# mian.net
KiCad netlist of a schematic drawn in Altium Designer
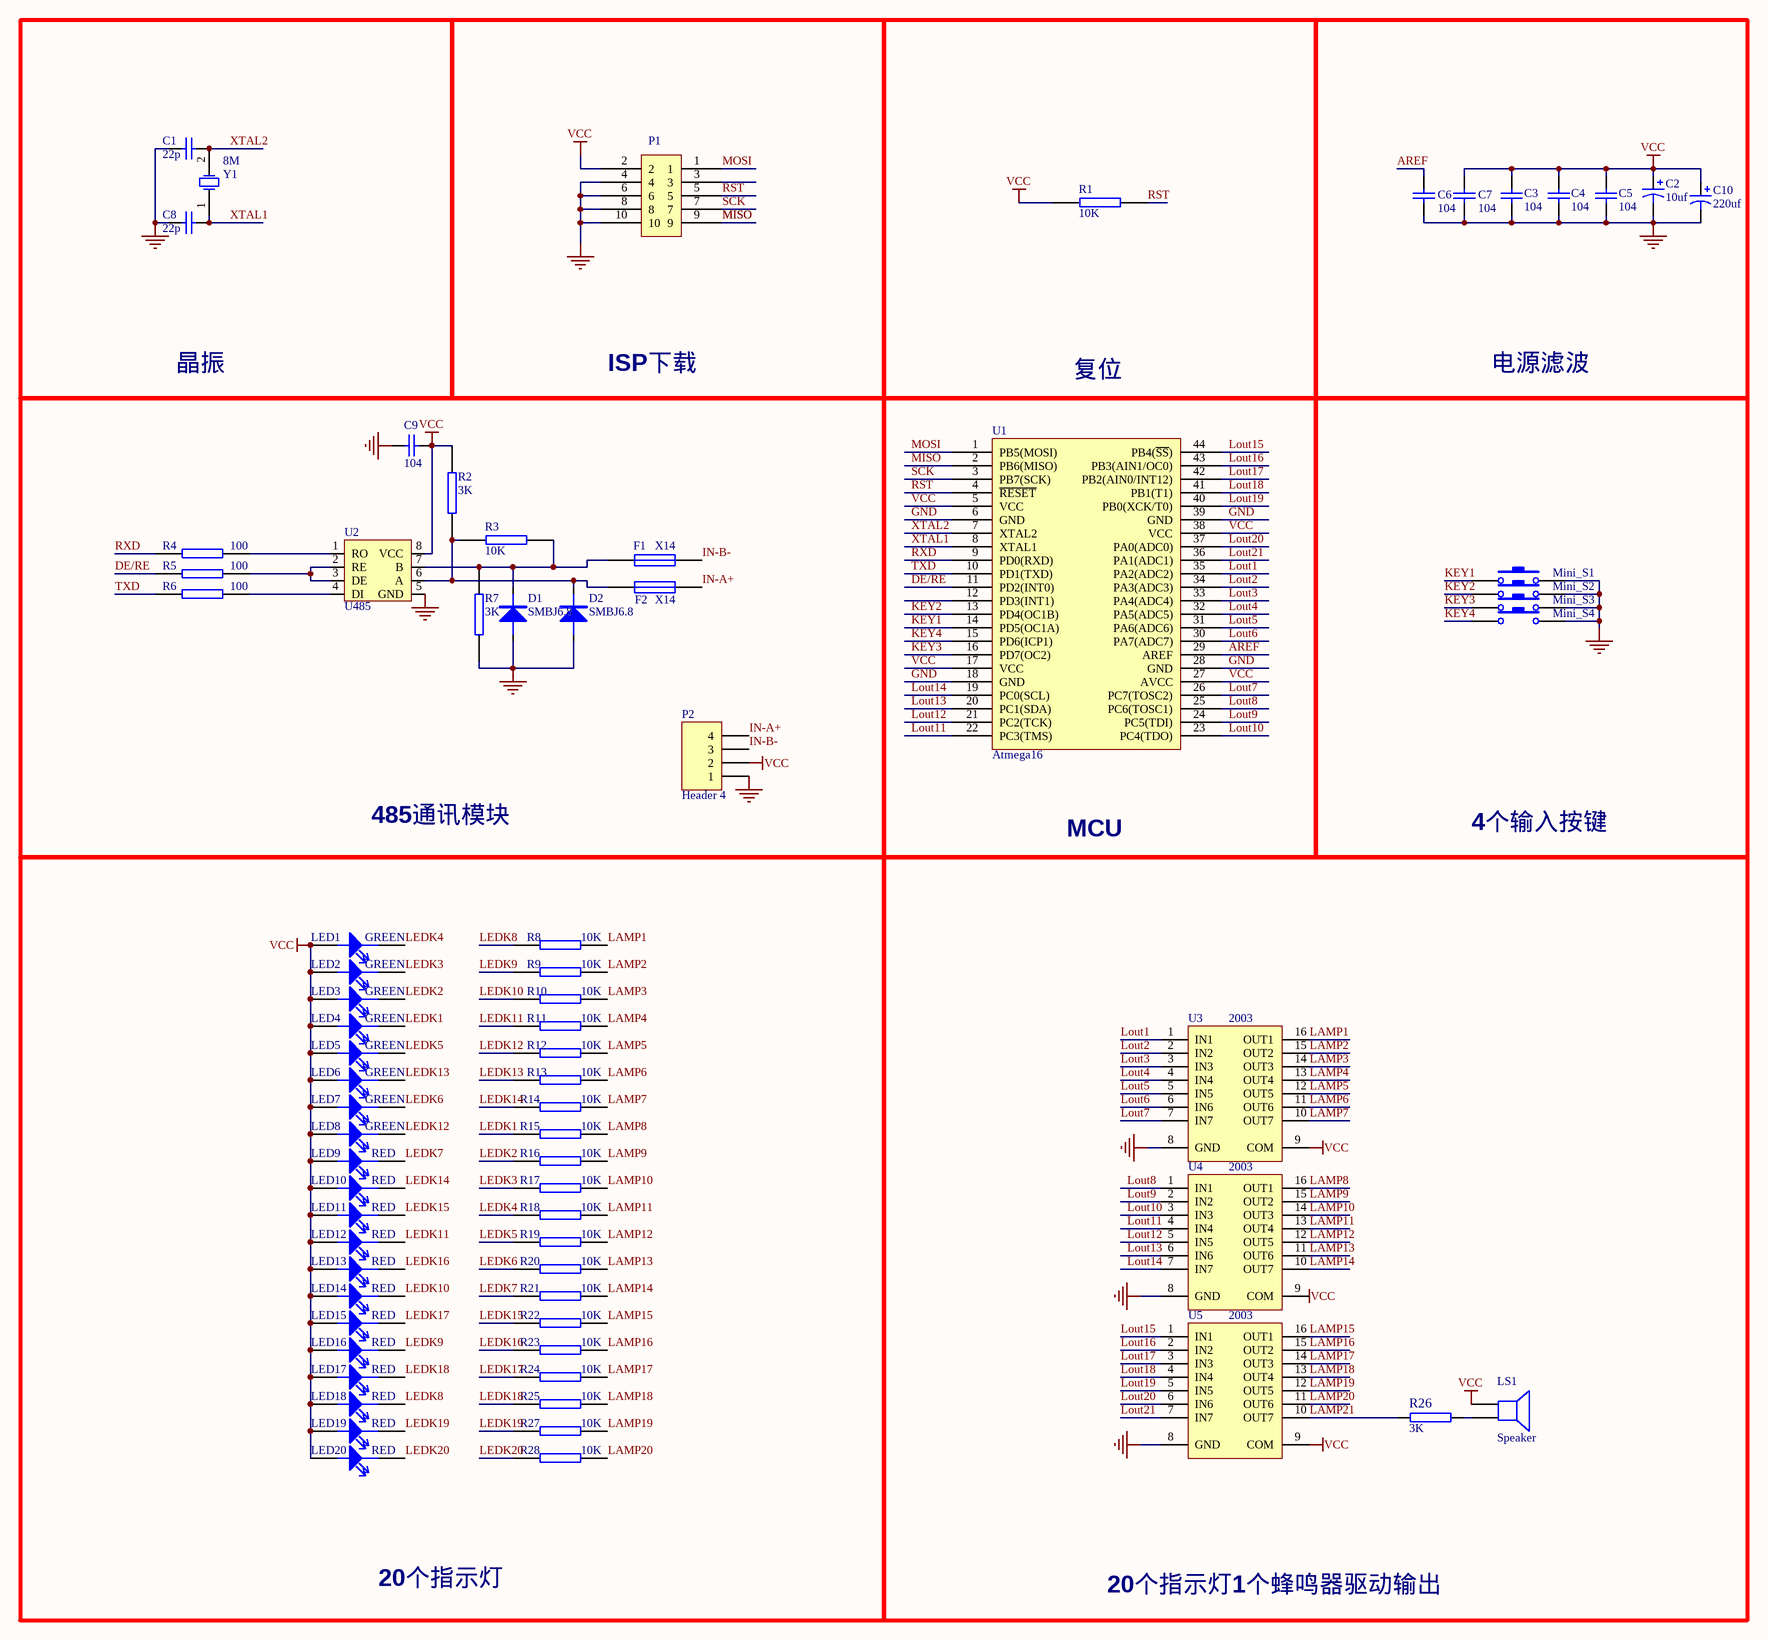
[diagram p0: mian.SchDoc]

(export (version "E")
  (design (tool "Eeschema 10.0.6"))
  (components
    (comp (ref "C1")
      (value "22p")
      (footprint "c0805c")
      (description "Capacitor")
      (fields (field (name "PUBLISHER") "Altium Limited"))
      (libsource (lib "*") (part "Cap"))
    )
    (comp (ref "C2")
      (value "10uf")
      (footprint "E6.5MM")
      (description "Polarized Capacitor (Radial)")
      (fields (field (name "PUBLISHER") "Altium Limited"))
      (libsource (lib "PCB_Project1") (part "Cap Pol1"))
    )
    (comp (ref "C3")
      (value "104")
      (footprint "c0805c")
      (description "Capacitor")
      (fields (field (name "PUBLISHER") "Altium Limited"))
      (libsource (lib "*") (part "Cap"))
    )
    (comp (ref "C4")
      (value "104")
      (footprint "c0805c")
      (description "Capacitor")
      (fields (field (name "PUBLISHER") "Altium Limited"))
      (libsource (lib "*") (part "Cap"))
    )
    (comp (ref "C5")
      (value "104")
      (footprint "c0805c")
      (description "Capacitor")
      (fields (field (name "PUBLISHER") "Altium Limited"))
      (libsource (lib "*") (part "Cap"))
    )
    (comp (ref "C6")
      (value "104")
      (footprint "c0805c")
      (description "Capacitor")
      (fields (field (name "PUBLISHER") "Altium Limited"))
      (libsource (lib "*") (part "Cap"))
    )
    (comp (ref "C7")
      (value "104")
      (footprint "c0805c")
      (description "Capacitor")
      (fields (field (name "PUBLISHER") "Altium Limited"))
      (libsource (lib "*") (part "Cap"))
    )
    (comp (ref "C8")
      (value "22p")
      (footprint "c0805c")
      (description "Capacitor")
      (fields (field (name "PUBLISHER") "Altium Limited"))
      (libsource (lib "*") (part "Cap"))
    )
    (comp (ref "C9")
      (value "104")
      (footprint "c0805c")
      (description "Capacitor")
      (fields (field (name "PUBLISHER") "Altium Limited"))
      (libsource (lib "*") (part "Cap"))
    )
    (comp (ref "C10")
      (value "220uf")
      (footprint "E6.5MM")
      (description "Polarized Capacitor (Radial)")
      (fields (field (name "PUBLISHER") "Altium Limited"))
      (libsource (lib "PCB_Project1") (part "Cap Pol1"))
    )
    (comp (ref "D1")
      (value "SMBJ6.8")
      (footprint "SMBJ_SMT")
      (description "Diode")
      (libsource (lib "*") (part "DIODE"))
    )
    (comp (ref "D2")
      (value "SMBJ6.8")
      (footprint "SMBJ_SMT")
      (description "Diode")
      (libsource (lib "*") (part "DIODE"))
    )
    (comp (ref "F1")
      (value "X14")
      (footprint "PPTC_SMT")
      (description "Fuse")
      (fields (field (name "PUBLISHER") "Altium Limited"))
      (libsource (lib "Miscellaneous Devices") (part "Fuse 1"))
    )
    (comp (ref "F2")
      (value "X14")
      (footprint "PPTC_SMT")
      (description "Fuse")
      (fields (field (name "PUBLISHER") "Altium Limited"))
      (libsource (lib "Miscellaneous Devices") (part "Fuse 1"))
    )
    (comp (ref "LED1")
      (value "GREEN")
      (footprint "PLED10*10")
      (description "Zener Diode")
      (libsource (lib "*") (part "LED"))
    )
    (comp (ref "LED2")
      (value "GREEN")
      (footprint "PLED10*10")
      (description "Zener Diode")
      (libsource (lib "*") (part "LED"))
    )
    (comp (ref "LED3")
      (value "GREEN")
      (footprint "PLED10*10")
      (description "Zener Diode")
      (libsource (lib "*") (part "LED"))
    )
    (comp (ref "LED4")
      (value "GREEN")
      (footprint "PLED10*10")
      (description "Zener Diode")
      (libsource (lib "*") (part "LED"))
    )
    (comp (ref "LED5")
      (value "GREEN")
      (footprint "PLED10*10")
      (description "Zener Diode")
      (libsource (lib "*") (part "LED"))
    )
    (comp (ref "LED6")
      (value "GREEN")
      (footprint "PLED10*10")
      (description "Zener Diode")
      (libsource (lib "*") (part "LED"))
    )
    (comp (ref "LED7")
      (value "GREEN")
      (footprint "PLED10*10")
      (description "Zener Diode")
      (libsource (lib "*") (part "LED"))
    )
    (comp (ref "LED8")
      (value "GREEN")
      (footprint "PLED10*10")
      (description "Zener Diode")
      (libsource (lib "*") (part "LED"))
    )
    (comp (ref "LED9")
      (value "RED")
      (footprint "PLED10*10")
      (description "Zener Diode")
      (libsource (lib "*") (part "LED"))
    )
    (comp (ref "LED10")
      (value "RED")
      (footprint "PLED10*10")
      (description "Zener Diode")
      (libsource (lib "*") (part "LED"))
    )
    (comp (ref "LED11")
      (value "RED")
      (footprint "PLED10*10")
      (description "Zener Diode")
      (libsource (lib "*") (part "LED"))
    )
    (comp (ref "LED12")
      (value "RED")
      (footprint "PLED10*10")
      (description "Zener Diode")
      (libsource (lib "*") (part "LED"))
    )
    (comp (ref "LED13")
      (value "RED")
      (footprint "PLED10*10")
      (description "Zener Diode")
      (libsource (lib "*") (part "LED"))
    )
    (comp (ref "LED14")
      (value "RED")
      (footprint "PLED10*10")
      (description "Zener Diode")
      (libsource (lib "*") (part "LED"))
    )
    (comp (ref "LED15")
      (value "RED")
      (footprint "PLED10*10")
      (description "Zener Diode")
      (libsource (lib "*") (part "LED"))
    )
    (comp (ref "LED16")
      (value "RED")
      (footprint "PLED10*10")
      (description "Zener Diode")
      (libsource (lib "*") (part "LED"))
    )
    (comp (ref "LED17")
      (value "RED")
      (footprint "PLED10*10")
      (description "Zener Diode")
      (libsource (lib "*") (part "LED"))
    )
    (comp (ref "LED18")
      (value "RED")
      (footprint "PLED10*10")
      (description "Zener Diode")
      (libsource (lib "*") (part "LED"))
    )
    (comp (ref "LED19")
      (value "RED")
      (footprint "PLED10*10")
      (description "Zener Diode")
      (libsource (lib "*") (part "LED"))
    )
    (comp (ref "LED20")
      (value "RED")
      (footprint "PLED10*10")
      (description "Zener Diode")
      (libsource (lib "*") (part "LED"))
    )
    (comp (ref "LS1")
      (value "Speaker")
      (footprint "SPK")
      (description "Loudspeaker")
      (fields (field (name "PUBLISHER") "Altium Limited"))
      (libsource (lib "Miscellaneous Devices") (part "Speaker"))
    )
    (comp (ref "Mini_S1")
      (value "~")
      (footprint "KEYL")
      (description "Switch")
      (fields (field (name "PUBLISHER") "Altium Limited"))
      (libsource (lib "Miscellaneous Devices") (part "SW-PB"))
    )
    (comp (ref "Mini_S2")
      (value "~")
      (footprint "KEYL")
      (description "Switch")
      (fields (field (name "PUBLISHER") "Altium Limited"))
      (libsource (lib "Miscellaneous Devices") (part "SW-PB"))
    )
    (comp (ref "Mini_S3")
      (value "~")
      (footprint "KEYL")
      (description "Switch")
      (fields (field (name "PUBLISHER") "Altium Limited"))
      (libsource (lib "Miscellaneous Devices") (part "SW-PB"))
    )
    (comp (ref "Mini_S4")
      (value "~")
      (footprint "KEYL")
      (description "Switch")
      (fields (field (name "PUBLISHER") "Altium Limited"))
      (libsource (lib "Miscellaneous Devices") (part "SW-PB"))
    )
    (comp (ref "P1") (value "CON10") (footprint "ISP") (libsource (lib "能迪SCH库") (part "SPI10")))
    (comp (ref "P2")
      (value "Header 4")
      (footprint "C3-4L")
      (description "Header, 4-Pin")
      (fields (field (name "PUBLISHER") "Altium Limited"))
      (libsource (lib "Miscellaneous Connectors") (part "Header 4"))
    )
    (comp (ref "R1") (value "10K") (footprint "0805C") (libsource (lib "*") (part "RES2")))
    (comp (ref "R2") (value "3K") (footprint "0805C") (libsource (lib "*") (part "RES2")))
    (comp (ref "R3") (value "10K") (footprint "0805C") (libsource (lib "*") (part "RES2")))
    (comp (ref "R4") (value "100") (footprint "0805C") (libsource (lib "") (part "RES2_1")))
    (comp (ref "R5") (value "100") (footprint "0805C") (libsource (lib "") (part "RES2_1")))
    (comp (ref "R6") (value "100") (footprint "0805C") (libsource (lib "") (part "RES2_1")))
    (comp (ref "R7") (value "3K") (footprint "0805C") (libsource (lib "*") (part "RES2")))
    (comp (ref "R8") (value "10K") (footprint "0805C") (libsource (lib "*") (part "RES2")))
    (comp (ref "R9") (value "10K") (footprint "0805C") (libsource (lib "*") (part "RES2")))
    (comp (ref "R10") (value "10K") (footprint "0805C") (libsource (lib "*") (part "RES2")))
    (comp (ref "R11") (value "10K") (footprint "0805C") (libsource (lib "*") (part "RES2")))
    (comp (ref "R12") (value "10K") (footprint "0805C") (libsource (lib "*") (part "RES2")))
    (comp (ref "R13") (value "10K") (footprint "0805C") (libsource (lib "*") (part "RES2")))
    (comp (ref "R14") (value "10K") (footprint "0805C") (libsource (lib "*") (part "RES2")))
    (comp (ref "R15") (value "10K") (footprint "0805C") (libsource (lib "*") (part "RES2")))
    (comp (ref "R16") (value "10K") (footprint "0805C") (libsource (lib "*") (part "RES2")))
    (comp (ref "R17") (value "10K") (footprint "0805C") (libsource (lib "*") (part "RES2")))
    (comp (ref "R18") (value "10K") (footprint "0805C") (libsource (lib "*") (part "RES2")))
    (comp (ref "R19") (value "10K") (footprint "0805C") (libsource (lib "*") (part "RES2")))
    (comp (ref "R20") (value "10K") (footprint "0805C") (libsource (lib "*") (part "RES2")))
    (comp (ref "R21") (value "10K") (footprint "0805C") (libsource (lib "*") (part "RES2")))
    (comp (ref "R22") (value "10K") (footprint "0805C") (libsource (lib "*") (part "RES2")))
    (comp (ref "R23") (value "10K") (footprint "0805C") (libsource (lib "*") (part "RES2")))
    (comp (ref "R24") (value "10K") (footprint "0805C") (libsource (lib "*") (part "RES2")))
    (comp (ref "R25") (value "10K") (footprint "0805C") (libsource (lib "*") (part "RES2")))
    (comp (ref "R26") (value "3K") (footprint "0805C") (libsource (lib "") (part "RES2_2")))
    (comp (ref "R27") (value "10K") (footprint "0805C") (libsource (lib "*") (part "RES2")))
    (comp (ref "R28") (value "10K") (footprint "0805C") (libsource (lib "*") (part "RES2")))
    (comp (ref "U1")
      (value "Atmega16")
      (footprint "QFP44")
      (libsource (lib "CL_FS_A(V1.0)") (part "Atmega16"))
    )
    (comp (ref "U2") (value "U485") (footprint "SOP8") (libsource (lib "POL485") (part "U485")))
    (comp (ref "U3")
      (value "2003")
      (footprint "SO_16")
      (description "High-Voltage, High-Current Darlington Array")
      (fields (field (name "PUBLISHER") "*"))
      (libsource (lib "*") (part "ULN2003A"))
    )
    (comp (ref "U4")
      (value "2003")
      (footprint "SO_16")
      (description "High-Voltage, High-Current Darlington Array")
      (fields (field (name "PUBLISHER") "*"))
      (libsource (lib "*") (part "ULN2003A"))
    )
    (comp (ref "U5")
      (value "2003")
      (footprint "SO_16")
      (description "High-Voltage, High-Current Darlington Array")
      (fields (field (name "PUBLISHER") "*"))
      (libsource (lib "*") (part "ULN2003A"))
    )
    (comp (ref "Y1")
      (value "8M")
      (footprint "XTP2")
      (description "Crystal Oscillator")
      (fields (field (name "PUBLISHER") "Altium Limited"))
      (libsource (lib "*") (part "XTAL"))
    )
  )
  (nets
    (net (code "1") (name "/AREF") (class "Default")
      (node (ref "C6") (pin "2") (pinfunction "2_2") (pintype "passive"))
      (node (ref "U1") (pin "29") (pinfunction "AREF_29") (pintype "passive"))
    )
    (net (code "2") (name "/DE{slash}RE") (class "Default")
      (node (ref "R5") (pin "2") (pinfunction "2_2") (pintype "passive"))
      (node (ref "U1") (pin "11") (pinfunction "PD2(INT0)_11") (pintype "passive"))
    )
    (net (code "3") (name "/IN-A+") (class "Default")
      (node (ref "F2") (pin "1") (pinfunction "1_1") (pintype "passive"))
      (node (ref "P2") (pin "4") (pinfunction "4_4") (pintype "passive"))
    )
    (net (code "4") (name "/IN-B-") (class "Default")
      (node (ref "F1") (pin "1") (pinfunction "1_1") (pintype "passive"))
      (node (ref "P2") (pin "3") (pinfunction "3_3") (pintype "passive"))
    )
    (net (code "5") (name "/KEY1") (class "Default")
      (node (ref "Mini_S1") (pin "1") (pinfunction "1_1") (pintype "passive"))
      (node (ref "U1") (pin "14") (pinfunction "PD5(OC1A)_14") (pintype "passive"))
    )
    (net (code "6") (name "/KEY2") (class "Default")
      (node (ref "Mini_S2") (pin "1") (pinfunction "1_1") (pintype "passive"))
      (node (ref "U1") (pin "13") (pinfunction "PD4(OC1B)_13") (pintype "passive"))
    )
    (net (code "7") (name "/KEY3") (class "Default")
      (node (ref "Mini_S3") (pin "1") (pinfunction "1_1") (pintype "passive"))
      (node (ref "U1") (pin "16") (pinfunction "PD7(OC2)_16") (pintype "passive"))
    )
    (net (code "8") (name "/KEY4") (class "Default")
      (node (ref "Mini_S4") (pin "1") (pinfunction "1_1") (pintype "passive"))
      (node (ref "U1") (pin "15") (pinfunction "PD6(ICP1)_15") (pintype "passive"))
    )
    (net (code "9") (name "/LAMP1") (class "Default")
      (node (ref "R8") (pin "2") (pinfunction "2_2") (pintype "passive"))
      (node (ref "U3") (pin "16") (pinfunction "OUT1_16") (pintype "open_collector"))
    )
    (net (code "10") (name "/LAMP2") (class "Default")
      (node (ref "R9") (pin "2") (pinfunction "2_2") (pintype "passive"))
      (node (ref "U3") (pin "15") (pinfunction "OUT2_15") (pintype "open_collector"))
    )
    (net (code "11") (name "/LAMP3") (class "Default")
      (node (ref "R10") (pin "2") (pinfunction "2_2") (pintype "passive"))
      (node (ref "U3") (pin "14") (pinfunction "OUT3_14") (pintype "open_collector"))
    )
    (net (code "12") (name "/LAMP4") (class "Default")
      (node (ref "R11") (pin "2") (pinfunction "2_2") (pintype "passive"))
      (node (ref "U3") (pin "13") (pinfunction "OUT4_13") (pintype "open_collector"))
    )
    (net (code "13") (name "/LAMP5") (class "Default")
      (node (ref "R12") (pin "2") (pinfunction "2_2") (pintype "passive"))
      (node (ref "U3") (pin "12") (pinfunction "OUT5_12") (pintype "open_collector"))
    )
    (net (code "14") (name "/LAMP6") (class "Default")
      (node (ref "R13") (pin "2") (pinfunction "2_2") (pintype "passive"))
      (node (ref "U3") (pin "11") (pinfunction "OUT6_11") (pintype "open_collector"))
    )
    (net (code "15") (name "/LAMP7") (class "Default")
      (node (ref "R14") (pin "2") (pinfunction "2_2") (pintype "passive"))
      (node (ref "U3") (pin "10") (pinfunction "OUT7_10") (pintype "open_collector"))
    )
    (net (code "16") (name "/LAMP8") (class "Default")
      (node (ref "R15") (pin "2") (pinfunction "2_2") (pintype "passive"))
      (node (ref "U4") (pin "16") (pinfunction "OUT1_16") (pintype "open_collector"))
    )
    (net (code "17") (name "/LAMP9") (class "Default")
      (node (ref "R16") (pin "2") (pinfunction "2_2") (pintype "passive"))
      (node (ref "U4") (pin "15") (pinfunction "OUT2_15") (pintype "open_collector"))
    )
    (net (code "18") (name "/LAMP10") (class "Default")
      (node (ref "R17") (pin "2") (pinfunction "2_2") (pintype "passive"))
      (node (ref "U4") (pin "14") (pinfunction "OUT3_14") (pintype "open_collector"))
    )
    (net (code "19") (name "/LAMP11") (class "Default")
      (node (ref "R18") (pin "2") (pinfunction "2_2") (pintype "passive"))
      (node (ref "U4") (pin "13") (pinfunction "OUT4_13") (pintype "open_collector"))
    )
    (net (code "20") (name "/LAMP12") (class "Default")
      (node (ref "R19") (pin "2") (pinfunction "2_2") (pintype "passive"))
      (node (ref "U4") (pin "12") (pinfunction "OUT5_12") (pintype "open_collector"))
    )
    (net (code "21") (name "/LAMP13") (class "Default")
      (node (ref "R20") (pin "2") (pinfunction "2_2") (pintype "passive"))
      (node (ref "U4") (pin "11") (pinfunction "OUT6_11") (pintype "open_collector"))
    )
    (net (code "22") (name "/LAMP14") (class "Default")
      (node (ref "R21") (pin "2") (pinfunction "2_2") (pintype "passive"))
      (node (ref "U4") (pin "10") (pinfunction "OUT7_10") (pintype "open_collector"))
    )
    (net (code "23") (name "/LAMP15") (class "Default")
      (node (ref "R22") (pin "2") (pinfunction "2_2") (pintype "passive"))
      (node (ref "U5") (pin "16") (pinfunction "OUT1_16") (pintype "open_collector"))
    )
    (net (code "24") (name "/LAMP16") (class "Default")
      (node (ref "R23") (pin "2") (pinfunction "2_2") (pintype "passive"))
      (node (ref "U5") (pin "15") (pinfunction "OUT2_15") (pintype "open_collector"))
    )
    (net (code "25") (name "/LAMP17") (class "Default")
      (node (ref "R24") (pin "2") (pinfunction "2_2") (pintype "passive"))
      (node (ref "U5") (pin "14") (pinfunction "OUT3_14") (pintype "open_collector"))
    )
    (net (code "26") (name "/LAMP18") (class "Default")
      (node (ref "R25") (pin "2") (pinfunction "2_2") (pintype "passive"))
      (node (ref "U5") (pin "13") (pinfunction "OUT4_13") (pintype "open_collector"))
    )
    (net (code "27") (name "/LAMP19") (class "Default")
      (node (ref "R27") (pin "2") (pinfunction "2_2") (pintype "passive"))
      (node (ref "U5") (pin "12") (pinfunction "OUT5_12") (pintype "open_collector"))
    )
    (net (code "28") (name "/LAMP20") (class "Default")
      (node (ref "R28") (pin "2") (pinfunction "2_2") (pintype "passive"))
      (node (ref "U5") (pin "11") (pinfunction "OUT6_11") (pintype "open_collector"))
    )
    (net (code "29") (name "/LAMP21") (class "Default")
      (node (ref "R26") (pin "1") (pintype "passive"))
      (node (ref "U5") (pin "10") (pinfunction "OUT7_10") (pintype "open_collector"))
    )
    (net (code "30") (name "/LEDK1") (class "Default")
      (node (ref "LED4") (pin "K") (pinfunction "K_K") (pintype "passive"))
      (node (ref "R15") (pin "1") (pinfunction "1_1") (pintype "passive"))
    )
    (net (code "31") (name "/LEDK2") (class "Default")
      (node (ref "LED3") (pin "K") (pinfunction "K_K") (pintype "passive"))
      (node (ref "R16") (pin "1") (pinfunction "1_1") (pintype "passive"))
    )
    (net (code "32") (name "/LEDK3") (class "Default")
      (node (ref "LED2") (pin "K") (pinfunction "K_K") (pintype "passive"))
      (node (ref "R17") (pin "1") (pinfunction "1_1") (pintype "passive"))
    )
    (net (code "33") (name "/LEDK4") (class "Default")
      (node (ref "LED1") (pin "K") (pinfunction "K_K") (pintype "passive"))
      (node (ref "R18") (pin "1") (pinfunction "1_1") (pintype "passive"))
    )
    (net (code "34") (name "/LEDK5") (class "Default")
      (node (ref "LED5") (pin "K") (pinfunction "K_K") (pintype "passive"))
      (node (ref "R19") (pin "1") (pinfunction "1_1") (pintype "passive"))
    )
    (net (code "35") (name "/LEDK6") (class "Default")
      (node (ref "LED7") (pin "K") (pinfunction "K_K") (pintype "passive"))
      (node (ref "R20") (pin "1") (pinfunction "1_1") (pintype "passive"))
    )
    (net (code "36") (name "/LEDK7") (class "Default")
      (node (ref "LED9") (pin "K") (pinfunction "K_K") (pintype "passive"))
      (node (ref "R21") (pin "1") (pinfunction "1_1") (pintype "passive"))
    )
    (net (code "37") (name "/LEDK8") (class "Default")
      (node (ref "LED18") (pin "K") (pinfunction "K_K") (pintype "passive"))
      (node (ref "R8") (pin "1") (pinfunction "1_1") (pintype "passive"))
    )
    (net (code "38") (name "/LEDK9") (class "Default")
      (node (ref "LED16") (pin "K") (pinfunction "K_K") (pintype "passive"))
      (node (ref "R9") (pin "1") (pinfunction "1_1") (pintype "passive"))
    )
    (net (code "39") (name "/LEDK10") (class "Default")
      (node (ref "LED14") (pin "K") (pinfunction "K_K") (pintype "passive"))
      (node (ref "R10") (pin "1") (pinfunction "1_1") (pintype "passive"))
    )
    (net (code "40") (name "/LEDK11") (class "Default")
      (node (ref "LED12") (pin "K") (pinfunction "K_K") (pintype "passive"))
      (node (ref "R11") (pin "1") (pinfunction "1_1") (pintype "passive"))
    )
    (net (code "41") (name "/LEDK12") (class "Default")
      (node (ref "LED8") (pin "K") (pinfunction "K_K") (pintype "passive"))
      (node (ref "R12") (pin "1") (pinfunction "1_1") (pintype "passive"))
    )
    (net (code "42") (name "/LEDK13") (class "Default")
      (node (ref "LED6") (pin "K") (pinfunction "K_K") (pintype "passive"))
      (node (ref "R13") (pin "1") (pinfunction "1_1") (pintype "passive"))
    )
    (net (code "43") (name "/LEDK14") (class "Default")
      (node (ref "LED10") (pin "K") (pinfunction "K_K") (pintype "passive"))
      (node (ref "R14") (pin "1") (pinfunction "1_1") (pintype "passive"))
    )
    (net (code "44") (name "/LEDK15") (class "Default")
      (node (ref "LED11") (pin "K") (pinfunction "K_K") (pintype "passive"))
      (node (ref "R22") (pin "1") (pinfunction "1_1") (pintype "passive"))
    )
    (net (code "45") (name "/LEDK16") (class "Default")
      (node (ref "LED13") (pin "K") (pinfunction "K_K") (pintype "passive"))
      (node (ref "R23") (pin "1") (pinfunction "1_1") (pintype "passive"))
    )
    (net (code "46") (name "/LEDK17") (class "Default")
      (node (ref "LED15") (pin "K") (pinfunction "K_K") (pintype "passive"))
      (node (ref "R24") (pin "1") (pinfunction "1_1") (pintype "passive"))
    )
    (net (code "47") (name "/LEDK18") (class "Default")
      (node (ref "LED17") (pin "K") (pinfunction "K_K") (pintype "passive"))
      (node (ref "R25") (pin "1") (pinfunction "1_1") (pintype "passive"))
    )
    (net (code "48") (name "/LEDK19") (class "Default")
      (node (ref "LED19") (pin "K") (pinfunction "K_K") (pintype "passive"))
      (node (ref "R27") (pin "1") (pinfunction "1_1") (pintype "passive"))
    )
    (net (code "49") (name "/LEDK20") (class "Default")
      (node (ref "LED20") (pin "K") (pinfunction "K_K") (pintype "passive"))
      (node (ref "R28") (pin "1") (pinfunction "1_1") (pintype "passive"))
    )
    (net (code "50") (name "/Lout1") (class "Default")
      (node (ref "U1") (pin "35") (pinfunction "PA2(ADC2)_35") (pintype "passive"))
      (node (ref "U3") (pin "1") (pinfunction "IN1_1") (pintype "passive"))
    )
    (net (code "51") (name "/Lout2") (class "Default")
      (node (ref "U1") (pin "34") (pinfunction "PA3(ADC3)_34") (pintype "passive"))
      (node (ref "U3") (pin "2") (pinfunction "IN2_2") (pintype "passive"))
    )
    (net (code "52") (name "/Lout3") (class "Default")
      (node (ref "U1") (pin "33") (pinfunction "PA4(ADC4)_33") (pintype "passive"))
      (node (ref "U3") (pin "3") (pinfunction "IN3_3") (pintype "passive"))
    )
    (net (code "53") (name "/Lout4") (class "Default")
      (node (ref "U1") (pin "32") (pinfunction "PA5(ADC5)_32") (pintype "passive"))
      (node (ref "U3") (pin "4") (pinfunction "IN4_4") (pintype "passive"))
    )
    (net (code "54") (name "/Lout5") (class "Default")
      (node (ref "U1") (pin "31") (pinfunction "PA6(ADC6)_31") (pintype "passive"))
      (node (ref "U3") (pin "5") (pinfunction "IN5_5") (pintype "passive"))
    )
    (net (code "55") (name "/Lout6") (class "Default")
      (node (ref "U1") (pin "30") (pinfunction "PA7(ADC7)_30") (pintype "passive"))
      (node (ref "U3") (pin "6") (pinfunction "IN6_6") (pintype "passive"))
    )
    (net (code "56") (name "/Lout7") (class "Default")
      (node (ref "U1") (pin "26") (pinfunction "PC7(TOSC2)_26") (pintype "passive"))
      (node (ref "U3") (pin "7") (pinfunction "IN7_7") (pintype "passive"))
    )
    (net (code "57") (name "/Lout8") (class "Default")
      (node (ref "U1") (pin "25") (pinfunction "PC6(TOSC1)_25") (pintype "passive"))
      (node (ref "U4") (pin "1") (pinfunction "IN1_1") (pintype "passive"))
    )
    (net (code "58") (name "/Lout9") (class "Default")
      (node (ref "U1") (pin "24") (pinfunction "PC5(TDI)_24") (pintype "passive"))
      (node (ref "U4") (pin "2") (pinfunction "IN2_2") (pintype "passive"))
    )
    (net (code "59") (name "/Lout10") (class "Default")
      (node (ref "U1") (pin "23") (pinfunction "PC4(TDO)_23") (pintype "passive"))
      (node (ref "U4") (pin "3") (pinfunction "IN3_3") (pintype "passive"))
    )
    (net (code "60") (name "/Lout11") (class "Default")
      (node (ref "U1") (pin "22") (pinfunction "PC3(TMS)_22") (pintype "passive"))
      (node (ref "U4") (pin "4") (pinfunction "IN4_4") (pintype "passive"))
    )
    (net (code "61") (name "/Lout12") (class "Default")
      (node (ref "U1") (pin "21") (pinfunction "PC2(TCK)_21") (pintype "passive"))
      (node (ref "U4") (pin "5") (pinfunction "IN5_5") (pintype "passive"))
    )
    (net (code "62") (name "/Lout13") (class "Default")
      (node (ref "U1") (pin "20") (pinfunction "PC1(SDA)_20") (pintype "passive"))
      (node (ref "U4") (pin "6") (pinfunction "IN6_6") (pintype "passive"))
    )
    (net (code "63") (name "/Lout14") (class "Default")
      (node (ref "U1") (pin "19") (pinfunction "PC0(SCL)_19") (pintype "passive"))
      (node (ref "U4") (pin "7") (pinfunction "IN7_7") (pintype "passive"))
    )
    (net (code "64") (name "/Lout15") (class "Default")
      (node (ref "U1") (pin "44") (pinfunction "PB4(~{SS})_44") (pintype "passive"))
      (node (ref "U5") (pin "1") (pinfunction "IN1_1") (pintype "passive"))
    )
    (net (code "65") (name "/Lout16") (class "Default")
      (node (ref "U1") (pin "43") (pinfunction "PB3(AIN1/OC0)_43") (pintype "passive"))
      (node (ref "U5") (pin "2") (pinfunction "IN2_2") (pintype "passive"))
    )
    (net (code "66") (name "/Lout17") (class "Default")
      (node (ref "U1") (pin "42") (pinfunction "PB2(AIN0/INT12)_42") (pintype "passive"))
      (node (ref "U5") (pin "3") (pinfunction "IN3_3") (pintype "passive"))
    )
    (net (code "67") (name "/Lout18") (class "Default")
      (node (ref "U1") (pin "41") (pinfunction "PB1(T1)_41") (pintype "passive"))
      (node (ref "U5") (pin "4") (pinfunction "IN4_4") (pintype "passive"))
    )
    (net (code "68") (name "/Lout19") (class "Default")
      (node (ref "U1") (pin "40") (pinfunction "PB0(XCK/T0)_40") (pintype "passive"))
      (node (ref "U5") (pin "5") (pinfunction "IN5_5") (pintype "passive"))
    )
    (net (code "69") (name "/Lout20") (class "Default")
      (node (ref "U1") (pin "37") (pinfunction "PA0(ADC0)_37") (pintype "passive"))
      (node (ref "U5") (pin "6") (pinfunction "IN6_6") (pintype "passive"))
    )
    (net (code "70") (name "/Lout21") (class "Default")
      (node (ref "U1") (pin "36") (pinfunction "PA1(ADC1)_36") (pintype "passive"))
      (node (ref "U5") (pin "7") (pinfunction "IN7_7") (pintype "passive"))
    )
    (net (code "71") (name "/MISO") (class "Default")
      (node (ref "P1") (pin "9") (pinfunction "9_9") (pintype "passive"))
      (node (ref "U1") (pin "2") (pinfunction "PB6(MISO)_2") (pintype "passive"))
    )
    (net (code "72") (name "/MOSI") (class "Default")
      (node (ref "P1") (pin "1") (pinfunction "1_1") (pintype "passive"))
      (node (ref "U1") (pin "1") (pinfunction "PB5(MOSI)_1") (pintype "passive"))
    )
    (net (code "73") (name "/RST") (class "Default")
      (node (ref "P1") (pin "5") (pinfunction "5_5") (pintype "passive"))
      (node (ref "R1") (pin "1") (pinfunction "1_1") (pintype "passive"))
      (node (ref "U1") (pin "4") (pinfunction "~{RESET}_4") (pintype "passive"))
    )
    (net (code "74") (name "/RXD") (class "Default")
      (node (ref "R4") (pin "2") (pinfunction "2_2") (pintype "passive"))
      (node (ref "U1") (pin "9") (pinfunction "PD0(RXD)_9") (pintype "passive"))
    )
    (net (code "75") (name "/SCK") (class "Default")
      (node (ref "P1") (pin "7") (pinfunction "7_7") (pintype "passive"))
      (node (ref "U1") (pin "3") (pinfunction "PB7(SCK)_3") (pintype "passive"))
    )
    (net (code "76") (name "/TXD") (class "Default")
      (node (ref "R6") (pin "2") (pinfunction "2_2") (pintype "passive"))
      (node (ref "U1") (pin "10") (pinfunction "PD1(TXD)_10") (pintype "passive"))
    )
    (net (code "77") (name "/XTAL1") (class "Default")
      (node (ref "C8") (pin "1") (pinfunction "1_1") (pintype "passive"))
      (node (ref "U1") (pin "8") (pinfunction "XTAL1_8") (pintype "passive"))
      (node (ref "Y1") (pin "1") (pinfunction "OSC1_1") (pintype "passive"))
    )
    (net (code "78") (name "/XTAL2") (class "Default")
      (node (ref "C1") (pin "1") (pinfunction "1_1") (pintype "passive"))
      (node (ref "U1") (pin "7") (pinfunction "XTAL2_7") (pintype "passive"))
      (node (ref "Y1") (pin "2") (pinfunction "OSC2_2") (pintype "passive"))
    )
    (net (code "79") (name "GND") (class "Default")
      (node (ref "C1") (pin "2") (pinfunction "2_2") (pintype "passive"))
      (node (ref "C10") (pin "2") (pinfunction "2_2") (pintype "passive"))
      (node (ref "C2") (pin "2") (pinfunction "2_2") (pintype "passive"))
      (node (ref "C3") (pin "1") (pinfunction "1_1") (pintype "passive"))
      (node (ref "C4") (pin "1") (pinfunction "1_1") (pintype "passive"))
      (node (ref "C5") (pin "2") (pinfunction "2_2") (pintype "passive"))
      (node (ref "C6") (pin "1") (pinfunction "1_1") (pintype "passive"))
      (node (ref "C7") (pin "1") (pinfunction "1_1") (pintype "passive"))
      (node (ref "C8") (pin "2") (pinfunction "2_2") (pintype "passive"))
      (node (ref "C9") (pin "2") (pinfunction "2_2") (pintype "passive"))
      (node (ref "D1") (pin "A") (pinfunction "A_A") (pintype "passive"))
      (node (ref "D2") (pin "A") (pinfunction "A_A") (pintype "passive"))
      (node (ref "Mini_S1") (pin "2") (pinfunction "2_2") (pintype "passive"))
      (node (ref "Mini_S2") (pin "2") (pinfunction "2_2") (pintype "passive"))
      (node (ref "Mini_S3") (pin "2") (pinfunction "2_2") (pintype "passive"))
      (node (ref "Mini_S4") (pin "2") (pinfunction "2_2") (pintype "passive"))
      (node (ref "P1") (pin "10") (pinfunction "10_10") (pintype "passive"))
      (node (ref "P1") (pin "4") (pinfunction "4_4") (pintype "passive"))
      (node (ref "P1") (pin "6") (pinfunction "6_6") (pintype "passive"))
      (node (ref "P1") (pin "8") (pinfunction "8_8") (pintype "passive"))
      (node (ref "P2") (pin "1") (pinfunction "1_1") (pintype "passive"))
      (node (ref "R7") (pin "1") (pinfunction "1_1") (pintype "passive"))
      (node (ref "U1") (pin "18") (pinfunction "GND_18") (pintype "passive"))
      (node (ref "U1") (pin "28") (pinfunction "GND_28") (pintype "passive"))
      (node (ref "U1") (pin "39") (pinfunction "GND_39") (pintype "passive"))
      (node (ref "U1") (pin "6") (pinfunction "GND_6") (pintype "passive"))
      (node (ref "U2") (pin "5") (pinfunction "GND_5") (pintype "passive"))
      (node (ref "U3") (pin "8") (pinfunction "GND_8") (pintype "power_in"))
      (node (ref "U4") (pin "8") (pinfunction "GND_8") (pintype "power_in"))
      (node (ref "U5") (pin "8") (pinfunction "GND_8") (pintype "power_in"))
    )
    (net (code "80") (name "Net-(LS1-Pad2)") (class "Default")
      (node (ref "LS1") (pin "2") (pinfunction "2_2") (pintype "passive"))
      (node (ref "R26") (pin "2") (pintype "passive"))
    )
    (net (code "81") (name "Net-(U2-A)") (class "Default")
      (node (ref "D2") (pin "K") (pinfunction "K_K") (pintype "passive"))
      (node (ref "F2") (pin "2") (pinfunction "2_2") (pintype "passive"))
      (node (ref "R2") (pin "2") (pinfunction "2_2") (pintype "passive"))
      (node (ref "R3") (pin "2") (pinfunction "2_2") (pintype "passive"))
      (node (ref "U2") (pin "6") (pinfunction "A_6") (pintype "passive"))
    )
    (net (code "82") (name "Net-(U2-B)") (class "Default")
      (node (ref "D1") (pin "K") (pinfunction "K_K") (pintype "passive"))
      (node (ref "F1") (pin "2") (pinfunction "2_2") (pintype "passive"))
      (node (ref "R3") (pin "1") (pinfunction "1_1") (pintype "passive"))
      (node (ref "R7") (pin "2") (pinfunction "2_2") (pintype "passive"))
      (node (ref "U2") (pin "7") (pinfunction "B_7") (pintype "passive"))
    )
    (net (code "83") (name "Net-(U2-DE)") (class "Default")
      (node (ref "R5") (pin "1") (pinfunction "1_1") (pintype "passive"))
      (node (ref "U2") (pin "2") (pinfunction "RE_2") (pintype "passive"))
      (node (ref "U2") (pin "3") (pinfunction "DE_3") (pintype "passive"))
    )
    (net (code "84") (name "Net-(U2-DI)") (class "Default")
      (node (ref "R6") (pin "1") (pinfunction "1_1") (pintype "passive"))
      (node (ref "U2") (pin "4") (pinfunction "DI_4") (pintype "passive"))
    )
    (net (code "85") (name "Net-(U2-RO)") (class "Default")
      (node (ref "R4") (pin "1") (pinfunction "1_1") (pintype "passive"))
      (node (ref "U2") (pin "1") (pinfunction "RO_1") (pintype "passive"))
    )
    (net (code "86") (name "VCC") (class "Default")
      (node (ref "C10") (pin "1") (pinfunction "1_1") (pintype "passive"))
      (node (ref "C2") (pin "1") (pinfunction "1_1") (pintype "passive"))
      (node (ref "C3") (pin "2") (pinfunction "2_2") (pintype "passive"))
      (node (ref "C4") (pin "2") (pinfunction "2_2") (pintype "passive"))
      (node (ref "C5") (pin "1") (pinfunction "1_1") (pintype "passive"))
      (node (ref "C7") (pin "2") (pinfunction "2_2") (pintype "passive"))
      (node (ref "C9") (pin "1") (pinfunction "1_1") (pintype "passive"))
      (node (ref "LED1") (pin "A") (pinfunction "A_A") (pintype "passive"))
      (node (ref "LED10") (pin "A") (pinfunction "A_A") (pintype "passive"))
      (node (ref "LED11") (pin "A") (pinfunction "A_A") (pintype "passive"))
      (node (ref "LED12") (pin "A") (pinfunction "A_A") (pintype "passive"))
      (node (ref "LED13") (pin "A") (pinfunction "A_A") (pintype "passive"))
      (node (ref "LED14") (pin "A") (pinfunction "A_A") (pintype "passive"))
      (node (ref "LED15") (pin "A") (pinfunction "A_A") (pintype "passive"))
      (node (ref "LED16") (pin "A") (pinfunction "A_A") (pintype "passive"))
      (node (ref "LED17") (pin "A") (pinfunction "A_A") (pintype "passive"))
      (node (ref "LED18") (pin "A") (pinfunction "A_A") (pintype "passive"))
      (node (ref "LED19") (pin "A") (pinfunction "A_A") (pintype "passive"))
      (node (ref "LED2") (pin "A") (pinfunction "A_A") (pintype "passive"))
      (node (ref "LED20") (pin "A") (pinfunction "A_A") (pintype "passive"))
      (node (ref "LED3") (pin "A") (pinfunction "A_A") (pintype "passive"))
      (node (ref "LED4") (pin "A") (pinfunction "A_A") (pintype "passive"))
      (node (ref "LED5") (pin "A") (pinfunction "A_A") (pintype "passive"))
      (node (ref "LED6") (pin "A") (pinfunction "A_A") (pintype "passive"))
      (node (ref "LED7") (pin "A") (pinfunction "A_A") (pintype "passive"))
      (node (ref "LED8") (pin "A") (pinfunction "A_A") (pintype "passive"))
      (node (ref "LED9") (pin "A") (pinfunction "A_A") (pintype "passive"))
      (node (ref "LS1") (pin "1") (pinfunction "1_1") (pintype "passive"))
      (node (ref "P1") (pin "2") (pinfunction "2_2") (pintype "passive"))
      (node (ref "P2") (pin "2") (pinfunction "2_2") (pintype "passive"))
      (node (ref "R1") (pin "2") (pinfunction "2_2") (pintype "passive"))
      (node (ref "R2") (pin "1") (pinfunction "1_1") (pintype "passive"))
      (node (ref "U1") (pin "17") (pinfunction "VCC_17") (pintype "passive"))
      (node (ref "U1") (pin "27") (pinfunction "AVCC_27") (pintype "passive"))
      (node (ref "U1") (pin "38") (pinfunction "VCC_38") (pintype "passive"))
      (node (ref "U1") (pin "5") (pinfunction "VCC_5") (pintype "passive"))
      (node (ref "U2") (pin "8") (pinfunction "VCC_8") (pintype "passive"))
      (node (ref "U3") (pin "9") (pinfunction "COM_9") (pintype "passive"))
      (node (ref "U4") (pin "9") (pinfunction "COM_9") (pintype "passive"))
      (node (ref "U5") (pin "9") (pinfunction "COM_9") (pintype "passive"))
    )
    (net (code "87") (name "unconnected-(P1-Pad3)") (class "Default")
      (node (ref "P1") (pin "3") (pinfunction "3_3") (pintype "passive"))
    )
    (net (code "88") (name "unconnected-(U1-PD3(INT1)-Pad12)") (class "Default")
      (node (ref "U1") (pin "12") (pinfunction "PD3(INT1)_12") (pintype "passive"))
    )
  )
)
